# module_2_ACCEL_GYRO.net
KiCad netlist of a schematic drawn in Altium Designer
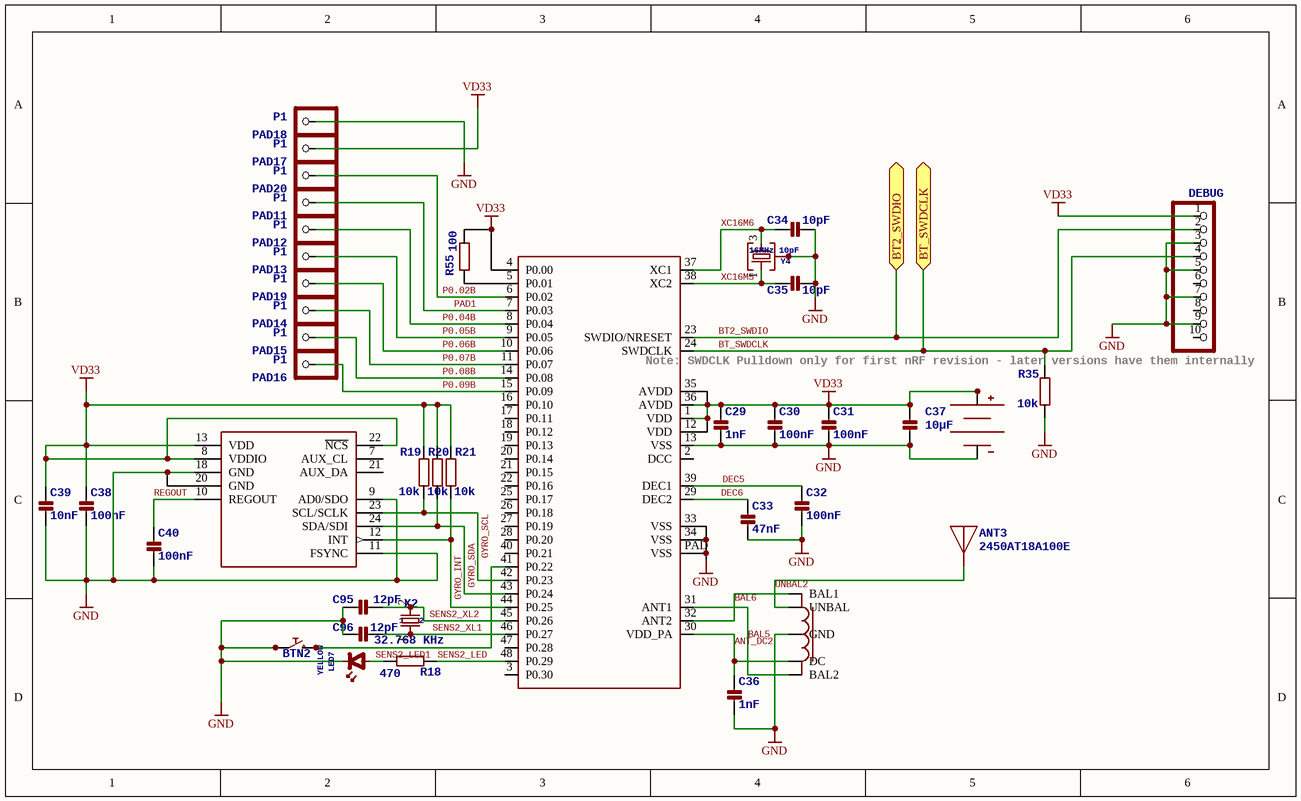
[diagram p0: module 2_ACCEL_GYRO.SchDoc]

(export (version "E")
  (design (tool "Eeschema 10.0.6"))
  (components
    (comp (ref "ANT3")
      (value "2450AT18A100E")
      (footprint "1206_MINIMELF_COMBO")
      (description "2.45 GHz Antenna")
      (libsource (lib "WunderBar_v101") (part "ANTENNA_MONOPOLE1206"))
    )
    (comp (ref "BALUN2")
      (value "2450BM14A0002T")
      (footprint "6-PIN-0603")
      (description "2.45 GHz Impedance Matched Balun-Filter")
      (libsource (lib "WunderBar_v101") (part "BALUN"))
    )
    (comp (ref "BAT2")
      (value "BATTERYBK-912")
      (footprint "BK-912")
      (description "Coin battery holder")
      (libsource (lib "WunderBar_v101") (part "BATTERYBK-912"))
    )
    (comp (ref "BT2")
      (value "NRF51822QFN48")
      (footprint "QFN48_EP")
      (description "Nordic Bluetooth 4.0 low energy modul")
      (libsource (lib "WunderBar_v101") (part "NRF51822QFN48"))
    )
    (comp (ref "BTN2")
      (value "Tact Sw 4.6x2.8")
      (footprint "CK-KMR2")
      (description "Push button")
      (libsource (lib "WunderBar_v101") (part "PUSHBUTTONKMR2XX"))
    )
    (comp (ref "C29")
      (value "1nF")
      (footprint "0402")
      (description "Ceramic Capacitor")
      (libsource (lib "WunderBar_v101") (part "CAP_CERAMIC0402"))
    )
    (comp (ref "C30")
      (value "100nF")
      (footprint "0402")
      (description "Ceramic Capacitor")
      (libsource (lib "WunderBar_v101") (part "CAP_CERAMIC0402"))
    )
    (comp (ref "C31")
      (value "100nF")
      (footprint "0402")
      (description "Ceramic Capacitor")
      (libsource (lib "WunderBar_v101") (part "CAP_CERAMIC0402"))
    )
    (comp (ref "C32")
      (value "100nF")
      (footprint "0402")
      (description "Ceramic Capacitor")
      (libsource (lib "WunderBar_v101") (part "CAP_CERAMIC0402"))
    )
    (comp (ref "C33")
      (value "47nF")
      (footprint "0402")
      (description "Ceramic Capacitor")
      (libsource (lib "WunderBar_v101") (part "CAP_CERAMIC0402"))
    )
    (comp (ref "C34")
      (value "10pF")
      (footprint "0402")
      (description "Ceramic Capacitor")
      (libsource (lib "") (part "CAP_CERAMIC0402_1"))
    )
    (comp (ref "C35")
      (value "10pF")
      (footprint "0402")
      (description "Ceramic Capacitor")
      (libsource (lib "") (part "CAP_CERAMIC0402_1"))
    )
    (comp (ref "C36")
      (value "1nF")
      (footprint "0402")
      (description "Ceramic Capacitor")
      (libsource (lib "WunderBar_v101") (part "CAP_CERAMIC0402"))
    )
    (comp (ref "C37")
      (value "10µF")
      (footprint "0603")
      (description "Ceramic Capacitor")
      (libsource (lib "WunderBar_v101") (part "CAP_CERAMIC0603"))
    )
    (comp (ref "C38")
      (value "100nF")
      (footprint "0402")
      (description "Ceramic Capacitor")
      (libsource (lib "WunderBar_v101") (part "CAP_CERAMIC0402"))
    )
    (comp (ref "C39")
      (value "10nF")
      (footprint "0402")
      (description "Ceramic Capacitor")
      (libsource (lib "WunderBar_v101") (part "CAP_CERAMIC0402"))
    )
    (comp (ref "C40")
      (value "100nF")
      (footprint "0402")
      (description "Ceramic Capacitor")
      (libsource (lib "WunderBar_v101") (part "CAP_CERAMIC0402"))
    )
    (comp (ref "C95")
      (value "12pF")
      (footprint "0402")
      (description "Ceramic Capacitor")
      (libsource (lib "") (part "CAP_CERAMIC0402_1"))
    )
    (comp (ref "C96")
      (value "12pF")
      (footprint "0402")
      (description "Ceramic Capacitor")
      (libsource (lib "") (part "CAP_CERAMIC0402_1"))
    )
    (comp (ref "DEBUG2")
      (value "DEBUG")
      (footprint "2X05_SMT")
      (description "cortex DEBUG connector")
      (libsource (lib "WunderBar_v101") (part "HEADER-2X5SMD-1.27MM"))
    )
    (comp (ref "LED7")
      (value "YELLOW")
      (footprint "0402_POLAR")
      (description "LED common")
      (libsource (lib "WunderBar_v101") (part "LED0402"))
    )
    (comp (ref "PAD11")
      (value "P1")
      (footprint "PCB_MEDIUM_RECT_PAD")
      (description "<b>PIN HEADER</b>")
      (libsource (lib "WunderBar_v101") (part "HEADER-1X1SMD_MEDIUM"))
    )
    (comp (ref "PAD12")
      (value "P1")
      (footprint "PCB_MEDIUM_RECT_PAD")
      (description "<b>PIN HEADER</b>")
      (libsource (lib "WunderBar_v101") (part "HEADER-1X1SMD_MEDIUM"))
    )
    (comp (ref "PAD13")
      (value "P1")
      (footprint "PCB_MEDIUM_RECT_PAD")
      (description "<b>PIN HEADER</b>")
      (libsource (lib "WunderBar_v101") (part "HEADER-1X1SMD_MEDIUM"))
    )
    (comp (ref "PAD14")
      (value "P1")
      (footprint "PCB_MEDIUM_RECT_PAD")
      (description "<b>PIN HEADER</b>")
      (libsource (lib "WunderBar_v101") (part "HEADER-1X1SMD_MEDIUM"))
    )
    (comp (ref "PAD15")
      (value "P1")
      (footprint "PCB_MEDIUM_RECT_PAD")
      (description "<b>PIN HEADER</b>")
      (libsource (lib "WunderBar_v101") (part "HEADER-1X1SMD_MEDIUM"))
    )
    (comp (ref "PAD16")
      (value "P1")
      (footprint "PCB_MEDIUM_RECT_PAD")
      (description "<b>PIN HEADER</b>")
      (libsource (lib "WunderBar_v101") (part "HEADER-1X1SMD_MEDIUM"))
    )
    (comp (ref "PAD17")
      (value "P1")
      (footprint "PCB_MEDIUM_RECT_PAD")
      (description "<b>PIN HEADER</b>")
      (libsource (lib "WunderBar_v101") (part "HEADER-1X1SMD_MEDIUM"))
    )
    (comp (ref "PAD18")
      (value "P1")
      (footprint "PCB_MEDIUM_RECT_PAD")
      (description "<b>PIN HEADER</b>")
      (libsource (lib "WunderBar_v101") (part "HEADER-1X1SMD_MEDIUM"))
    )
    (comp (ref "PAD19")
      (value "P1")
      (footprint "PCB_MEDIUM_RECT_PAD")
      (description "<b>PIN HEADER</b>")
      (libsource (lib "WunderBar_v101") (part "HEADER-1X1SMD_MEDIUM"))
    )
    (comp (ref "PAD20")
      (value "P1")
      (footprint "PCB_MEDIUM_RECT_PAD")
      (description "<b>PIN HEADER</b>")
      (libsource (lib "WunderBar_v101") (part "HEADER-1X1SMD_MEDIUM"))
    )
    (comp (ref "R18")
      (value "470")
      (footprint "0402")
      (description "RESISTOR")
      (libsource (lib "WunderBar_v101") (part "R-EU_0402"))
    )
    (comp (ref "R19")
      (value "10k")
      (footprint "0402")
      (description "RESISTOR")
      (libsource (lib "WunderBar_v101") (part "R-EU_0402"))
    )
    (comp (ref "R20")
      (value "10k")
      (footprint "0402")
      (description "RESISTOR")
      (libsource (lib "WunderBar_v101") (part "R-EU_0402"))
    )
    (comp (ref "R21")
      (value "10k")
      (footprint "0402")
      (description "RESISTOR")
      (libsource (lib "WunderBar_v101") (part "R-EU_0402"))
    )
    (comp (ref "R35")
      (value "10k")
      (footprint "0402")
      (description "RESISTOR")
      (libsource (lib "WunderBar_v101") (part "R-EU_0402"))
    )
    (comp (ref "R55")
      (value "100")
      (footprint "0402")
      (description "RESISTOR")
      (libsource (lib "WunderBar_v101") (part "R-EU_0402"))
    )
    (comp (ref "SENSE2")
      (value "MPU6500QFN")
      (footprint "QFN24-0.4")
      (description "Invensense MPU6500 combined gyro + accelerometer, I2C")
      (libsource (lib "WunderBar_v101") (part "MPU6500QFN"))
    )
    (comp (ref "X2")
      (value "32.768 KHz")
      (footprint "1206_MINIMELF_COMBO")
      (description "CL05C120JB5")
      (fields (field (name "1") "1") (field (name "2") "2"))
      (libsource (lib "WunderBar_v101") (part "CRYSTAL1206"))
    )
    (comp (ref "Y4")
      (value "16MHz 10pF")
      (footprint "CRYSTAL25X20")
      (description "16MHz crystal 2.5x2mm")
      (libsource (lib "WunderBar_v101") (part "CRYSTAL_WITH_GROUND25X20"))
    )
  )
  (nets
    (net (code "1") (name "/ANT_DC2") (class "Default")
      (node (ref "BALUN2") (pin "5") (pinfunction "DC_5") (pintype "power_in"))
      (node (ref "BT2") (pin "30") (pinfunction "VDD_PA_30") (pintype "passive"))
      (node (ref "C36") (pin "1") (pinfunction "1_1") (pintype "passive"))
    )
    (net (code "2") (name "/BAL5") (class "Default")
      (node (ref "BALUN2") (pin "4") (pinfunction "BAL2_4") (pintype "passive"))
      (node (ref "BT2") (pin "31") (pinfunction "ANT1_31") (pintype "passive"))
    )
    (net (code "3") (name "/BAL6") (class "Default")
      (node (ref "BALUN2") (pin "3") (pinfunction "BAL1_3") (pintype "passive"))
      (node (ref "BT2") (pin "32") (pinfunction "ANT2_32") (pintype "passive"))
    )
    (net (code "4") (name "/BT2_SWDIO") (class "Default")
      (node (ref "BT2") (pin "23") (pinfunction "SWDIO/NRESET_23") (pintype "passive"))
      (node (ref "DEBUG2") (pin "2") (pinfunction "2_2") (pintype "passive"))
    )
    (net (code "5") (name "/BT_SWDCLK") (class "Default")
      (node (ref "BT2") (pin "24") (pinfunction "SWDCLK_24") (pintype "passive"))
      (node (ref "DEBUG2") (pin "4") (pinfunction "4_4") (pintype "passive"))
      (node (ref "R35") (pin "2") (pinfunction "2_2") (pintype "passive"))
    )
    (net (code "6") (name "/DEC5") (class "Default")
      (node (ref "BT2") (pin "39") (pinfunction "DEC1_39") (pintype "passive"))
      (node (ref "C32") (pin "1") (pinfunction "1_1") (pintype "passive"))
    )
    (net (code "7") (name "/DEC6") (class "Default")
      (node (ref "BT2") (pin "29") (pinfunction "DEC2_29") (pintype "passive"))
      (node (ref "C33") (pin "1") (pinfunction "1_1") (pintype "passive"))
    )
    (net (code "8") (name "/GYRO_INT") (class "Default")
      (node (ref "BT2") (pin "44") (pinfunction "P0.25_44") (pintype "passive"))
      (node (ref "R21") (pin "1") (pinfunction "1_1") (pintype "passive"))
      (node (ref "SENSE2") (pin "12") (pinfunction "INT_12") (pintype "output"))
    )
    (net (code "9") (name "/GYRO_SCL") (class "Default")
      (node (ref "BT2") (pin "42") (pinfunction "P0.23_42") (pintype "passive"))
      (node (ref "R19") (pin "1") (pinfunction "1_1") (pintype "passive"))
      (node (ref "SENSE2") (pin "23") (pinfunction "SCL/SCLK_23") (pintype "passive"))
    )
    (net (code "10") (name "/GYRO_SDA") (class "Default")
      (node (ref "BT2") (pin "43") (pinfunction "P0.24_43") (pintype "passive"))
      (node (ref "R20") (pin "1") (pinfunction "1_1") (pintype "passive"))
      (node (ref "SENSE2") (pin "24") (pinfunction "SDA/SDI_24") (pintype "passive"))
    )
    (net (code "11") (name "/P0.02B") (class "Default")
      (node (ref "BT2") (pin "6") (pinfunction "P0.02_6") (pintype "passive"))
      (node (ref "PAD20") (pin "1") (pinfunction "1_1") (pintype "passive"))
    )
    (net (code "12") (name "/P0.04B") (class "Default")
      (node (ref "BT2") (pin "8") (pinfunction "P0.04_8") (pintype "passive"))
      (node (ref "PAD12") (pin "1") (pinfunction "1_1") (pintype "passive"))
    )
    (net (code "13") (name "/P0.05B") (class "Default")
      (node (ref "BT2") (pin "9") (pinfunction "P0.05_9") (pintype "passive"))
      (node (ref "PAD13") (pin "1") (pinfunction "1_1") (pintype "passive"))
    )
    (net (code "14") (name "/P0.06B") (class "Default")
      (node (ref "BT2") (pin "10") (pinfunction "P0.06_10") (pintype "passive"))
      (node (ref "PAD19") (pin "1") (pinfunction "1_1") (pintype "passive"))
    )
    (net (code "15") (name "/P0.07B") (class "Default")
      (node (ref "BT2") (pin "11") (pinfunction "P0.07_11") (pintype "passive"))
      (node (ref "PAD14") (pin "1") (pinfunction "1_1") (pintype "passive"))
    )
    (net (code "16") (name "/P0.08B") (class "Default")
      (node (ref "BT2") (pin "14") (pinfunction "P0.08_14") (pintype "passive"))
      (node (ref "PAD15") (pin "1") (pinfunction "1_1") (pintype "passive"))
    )
    (net (code "17") (name "/P0.09B") (class "Default")
      (node (ref "BT2") (pin "15") (pinfunction "P0.09_15") (pintype "passive"))
      (node (ref "PAD16") (pin "1") (pinfunction "1_1") (pintype "passive"))
    )
    (net (code "18") (name "/PAD1") (class "Default")
      (node (ref "BT2") (pin "7") (pinfunction "P0.03_7") (pintype "passive"))
      (node (ref "PAD11") (pin "1") (pinfunction "1_1") (pintype "passive"))
    )
    (net (code "19") (name "/REGOUT") (class "Default")
      (node (ref "C40") (pin "1") (pinfunction "1_1") (pintype "passive"))
      (node (ref "SENSE2") (pin "10") (pinfunction "REGOUT_10") (pintype "passive"))
    )
    (net (code "20") (name "/SENS2_LED") (class "Default")
      (node (ref "BT2") (pin "48") (pinfunction "P0.29_48") (pintype "passive"))
      (node (ref "R18") (pin "1") (pinfunction "1_1") (pintype "passive"))
    )
    (net (code "21") (name "/SENS2_LED1") (class "Default")
      (node (ref "LED7") (pin "A") (pinfunction "ANODE_A") (pintype "passive"))
      (node (ref "R18") (pin "2") (pinfunction "2_2") (pintype "passive"))
    )
    (net (code "22") (name "/SENS2_XL1") (class "Default")
      (node (ref "BT2") (pin "46") (pinfunction "P0.27_46") (pintype "passive"))
      (node (ref "C96") (pin "2") (pinfunction "2_2") (pintype "passive"))
      (node (ref "X2") (pin "1") (pinfunction "1_1") (pintype "passive"))
    )
    (net (code "23") (name "/SENS2_XL2") (class "Default")
      (node (ref "BT2") (pin "45") (pinfunction "P0.26_45") (pintype "passive"))
      (node (ref "C95") (pin "2") (pinfunction "2_2") (pintype "passive"))
      (node (ref "X2") (pin "2") (pinfunction "2_2") (pintype "passive"))
    )
    (net (code "24") (name "/UNBAL2") (class "Default")
      (node (ref "ANT3") (pin "1") (pinfunction "ANT_1") (pintype "passive"))
      (node (ref "BALUN2") (pin "1") (pinfunction "UNBAL_1") (pintype "passive"))
    )
    (net (code "25") (name "/XC16M5") (class "Default")
      (node (ref "BT2") (pin "38") (pinfunction "XC2_38") (pintype "passive"))
      (node (ref "C35") (pin "1") (pinfunction "1_1") (pintype "passive"))
      (node (ref "Y4") (pin "1") (pinfunction "1_1") (pintype "passive"))
    )
    (net (code "26") (name "/XC16M6") (class "Default")
      (node (ref "BT2") (pin "37") (pinfunction "XC1_37") (pintype "passive"))
      (node (ref "C34") (pin "1") (pinfunction "1_1") (pintype "passive"))
      (node (ref "Y4") (pin "3") (pinfunction "3_3") (pintype "passive"))
    )
    (net (code "27") (name "GND") (class "Default")
      (node (ref "BALUN2") (pin "2") (pinfunction "GND_2") (pintype "power_in"))
      (node (ref "BAT2") (pin "-") (pinfunction "-_-") (pintype "power_in"))
      (node (ref "BT2") (pin "13") (pinfunction "VSS_13") (pintype "passive"))
      (node (ref "BT2") (pin "33") (pinfunction "VSS_33") (pintype "passive"))
      (node (ref "BT2") (pin "34") (pinfunction "VSS_34") (pintype "passive"))
      (node (ref "BT2") (pin "PAD") (pinfunction "VSS_PAD") (pintype "passive"))
      (node (ref "BTN2") (pin "P1") (pinfunction "1_P1") (pintype "passive"))
      (node (ref "BTN2") (pin "P2") (pinfunction "2_P2") (pintype "passive"))
      (node (ref "C29") (pin "2") (pinfunction "2_2") (pintype "passive"))
      (node (ref "C30") (pin "2") (pinfunction "2_2") (pintype "passive"))
      (node (ref "C31") (pin "2") (pinfunction "2_2") (pintype "passive"))
      (node (ref "C32") (pin "2") (pinfunction "2_2") (pintype "passive"))
      (node (ref "C33") (pin "2") (pinfunction "2_2") (pintype "passive"))
      (node (ref "C34") (pin "2") (pinfunction "2_2") (pintype "passive"))
      (node (ref "C35") (pin "2") (pinfunction "2_2") (pintype "passive"))
      (node (ref "C36") (pin "2") (pinfunction "2_2") (pintype "passive"))
      (node (ref "C37") (pin "2") (pinfunction "P2_2") (pintype "passive"))
      (node (ref "C38") (pin "2") (pinfunction "2_2") (pintype "passive"))
      (node (ref "C39") (pin "2") (pinfunction "2_2") (pintype "passive"))
      (node (ref "C40") (pin "2") (pinfunction "2_2") (pintype "passive"))
      (node (ref "C95") (pin "1") (pinfunction "1_1") (pintype "passive"))
      (node (ref "C96") (pin "1") (pinfunction "1_1") (pintype "passive"))
      (node (ref "DEBUG2") (pin "3") (pinfunction "3_3") (pintype "passive"))
      (node (ref "DEBUG2") (pin "5") (pinfunction "5_5") (pintype "passive"))
      (node (ref "DEBUG2") (pin "7") (pinfunction "7_7") (pintype "passive"))
      (node (ref "DEBUG2") (pin "9") (pinfunction "9_9") (pintype "passive"))
      (node (ref "LED7") (pin "K") (pinfunction "CATHODE_K") (pintype "passive"))
      (node (ref "PAD18") (pin "1") (pinfunction "1_1") (pintype "passive"))
      (node (ref "R35") (pin "1") (pinfunction "1_1") (pintype "passive"))
      (node (ref "SENSE2") (pin "11") (pinfunction "FSYNC_11") (pintype "passive"))
      (node (ref "SENSE2") (pin "18") (pinfunction "GND_18") (pintype "power_in"))
      (node (ref "SENSE2") (pin "20") (pinfunction "GND_20") (pintype "power_in"))
      (node (ref "SENSE2") (pin "9") (pinfunction "AD0/SDO_9") (pintype "passive"))
      (node (ref "Y4") (pin "2") (pinfunction "2_2") (pintype "power_in"))
      (node (ref "Y4") (pin "4") (pinfunction "4_4") (pintype "power_in"))
    )
    (net (code "28") (name "Net-(BT2-P0.01)") (class "Default")
      (node (ref "BT2") (pin "5") (pinfunction "P0.01_5") (pintype "passive"))
      (node (ref "R55") (pin "2") (pinfunction "2_2") (pintype "passive"))
    )
    (net (code "29") (name "Net-(BT2-P0.22)") (class "Default")
      (node (ref "BT2") (pin "41") (pinfunction "P0.22_41") (pintype "passive"))
      (node (ref "BTN2") (pin "P3") (pinfunction "3_P3") (pintype "passive"))
      (node (ref "BTN2") (pin "P4") (pinfunction "4_P4") (pintype "passive"))
    )
    (net (code "30") (name "VD33") (class "Default")
      (node (ref "BAT2") (pin "+1") (pinfunction "+_+1") (pintype "power_in"))
      (node (ref "BAT2") (pin "+2") (pinfunction "+_+2") (pintype "power_in"))
      (node (ref "BT2") (pin "1") (pinfunction "VDD_1") (pintype "passive"))
      (node (ref "BT2") (pin "12") (pinfunction "VDD_12") (pintype "passive"))
      (node (ref "BT2") (pin "35") (pinfunction "AVDD_35") (pintype "passive"))
      (node (ref "BT2") (pin "36") (pinfunction "AVDD_36") (pintype "passive"))
      (node (ref "BT2") (pin "4") (pinfunction "P0.00_4") (pintype "passive"))
      (node (ref "C29") (pin "1") (pinfunction "1_1") (pintype "passive"))
      (node (ref "C30") (pin "1") (pinfunction "1_1") (pintype "passive"))
      (node (ref "C31") (pin "1") (pinfunction "1_1") (pintype "passive"))
      (node (ref "C37") (pin "1") (pinfunction "P1_1") (pintype "passive"))
      (node (ref "C38") (pin "1") (pinfunction "1_1") (pintype "passive"))
      (node (ref "C39") (pin "1") (pinfunction "1_1") (pintype "passive"))
      (node (ref "DEBUG2") (pin "1") (pinfunction "1_1") (pintype "passive"))
      (node (ref "PAD17") (pin "1") (pinfunction "1_1") (pintype "passive"))
      (node (ref "R19") (pin "2") (pinfunction "2_2") (pintype "passive"))
      (node (ref "R20") (pin "2") (pinfunction "2_2") (pintype "passive"))
      (node (ref "R21") (pin "2") (pinfunction "2_2") (pintype "passive"))
      (node (ref "R55") (pin "1") (pinfunction "1_1") (pintype "passive"))
      (node (ref "SENSE2") (pin "13") (pinfunction "VDD_13") (pintype "power_in"))
      (node (ref "SENSE2") (pin "22") (pinfunction "~{NCS}_22") (pintype "passive"))
      (node (ref "SENSE2") (pin "8") (pinfunction "VDDIO_8") (pintype "passive"))
    )
    (net (code "31") (name "unconnected-(BT2-DCC-Pad2)") (class "Default")
      (node (ref "BT2") (pin "2") (pinfunction "DCC_2") (pintype "passive"))
    )
    (net (code "32") (name "unconnected-(BT2-P0.10-Pad16)") (class "Default")
      (node (ref "BT2") (pin "16") (pinfunction "P0.10_16") (pintype "passive"))
    )
    (net (code "33") (name "unconnected-(BT2-P0.11-Pad17)") (class "Default")
      (node (ref "BT2") (pin "17") (pinfunction "P0.11_17") (pintype "passive"))
    )
    (net (code "34") (name "unconnected-(BT2-P0.12-Pad18)") (class "Default")
      (node (ref "BT2") (pin "18") (pinfunction "P0.12_18") (pintype "passive"))
    )
    (net (code "35") (name "unconnected-(BT2-P0.13-Pad19)") (class "Default")
      (node (ref "BT2") (pin "19") (pinfunction "P0.13_19") (pintype "passive"))
    )
    (net (code "36") (name "unconnected-(BT2-P0.14-Pad20)") (class "Default")
      (node (ref "BT2") (pin "20") (pinfunction "P0.14_20") (pintype "passive"))
    )
    (net (code "37") (name "unconnected-(BT2-P0.15-Pad21)") (class "Default")
      (node (ref "BT2") (pin "21") (pinfunction "P0.15_21") (pintype "passive"))
    )
    (net (code "38") (name "unconnected-(BT2-P0.16-Pad22)") (class "Default")
      (node (ref "BT2") (pin "22") (pinfunction "P0.16_22") (pintype "passive"))
    )
    (net (code "39") (name "unconnected-(BT2-P0.17-Pad25)") (class "Default")
      (node (ref "BT2") (pin "25") (pinfunction "P0.17_25") (pintype "passive"))
    )
    (net (code "40") (name "unconnected-(BT2-P0.18-Pad26)") (class "Default")
      (node (ref "BT2") (pin "26") (pinfunction "P0.18_26") (pintype "passive"))
    )
    (net (code "41") (name "unconnected-(BT2-P0.19-Pad27)") (class "Default")
      (node (ref "BT2") (pin "27") (pinfunction "P0.19_27") (pintype "passive"))
    )
    (net (code "42") (name "unconnected-(BT2-P0.20-Pad28)") (class "Default")
      (node (ref "BT2") (pin "28") (pinfunction "P0.20_28") (pintype "passive"))
    )
    (net (code "43") (name "unconnected-(BT2-P0.21-Pad40)") (class "Default")
      (node (ref "BT2") (pin "40") (pinfunction "P0.21_40") (pintype "passive"))
    )
    (net (code "44") (name "unconnected-(BT2-P0.28-Pad47)") (class "Default")
      (node (ref "BT2") (pin "47") (pinfunction "P0.28_47") (pintype "passive"))
    )
    (net (code "45") (name "unconnected-(BT2-P0.30-Pad3)") (class "Default")
      (node (ref "BT2") (pin "3") (pinfunction "P0.30_3") (pintype "passive"))
    )
    (net (code "46") (name "unconnected-(DEBUG2-Pad6)") (class "Default")
      (node (ref "DEBUG2") (pin "6") (pinfunction "6_6") (pintype "passive"))
    )
    (net (code "47") (name "unconnected-(DEBUG2-Pad8)") (class "Default")
      (node (ref "DEBUG2") (pin "8") (pinfunction "8_8") (pintype "passive"))
    )
    (net (code "48") (name "unconnected-(DEBUG2-Pad10)") (class "Default")
      (node (ref "DEBUG2") (pin "10") (pinfunction "10_10") (pintype "passive"))
    )
    (net (code "49") (name "unconnected-(SENSE2-AUX_CL-Pad7)") (class "Default")
      (node (ref "SENSE2") (pin "7") (pinfunction "AUX_CL_7") (pintype "passive"))
    )
    (net (code "50") (name "unconnected-(SENSE2-AUX_DA-Pad21)") (class "Default")
      (node (ref "SENSE2") (pin "21") (pinfunction "AUX_DA_21") (pintype "passive"))
    )
  )
)
